# DVT-Discrete-2.net
KiCad netlist of a schematic drawn in Altium Designer
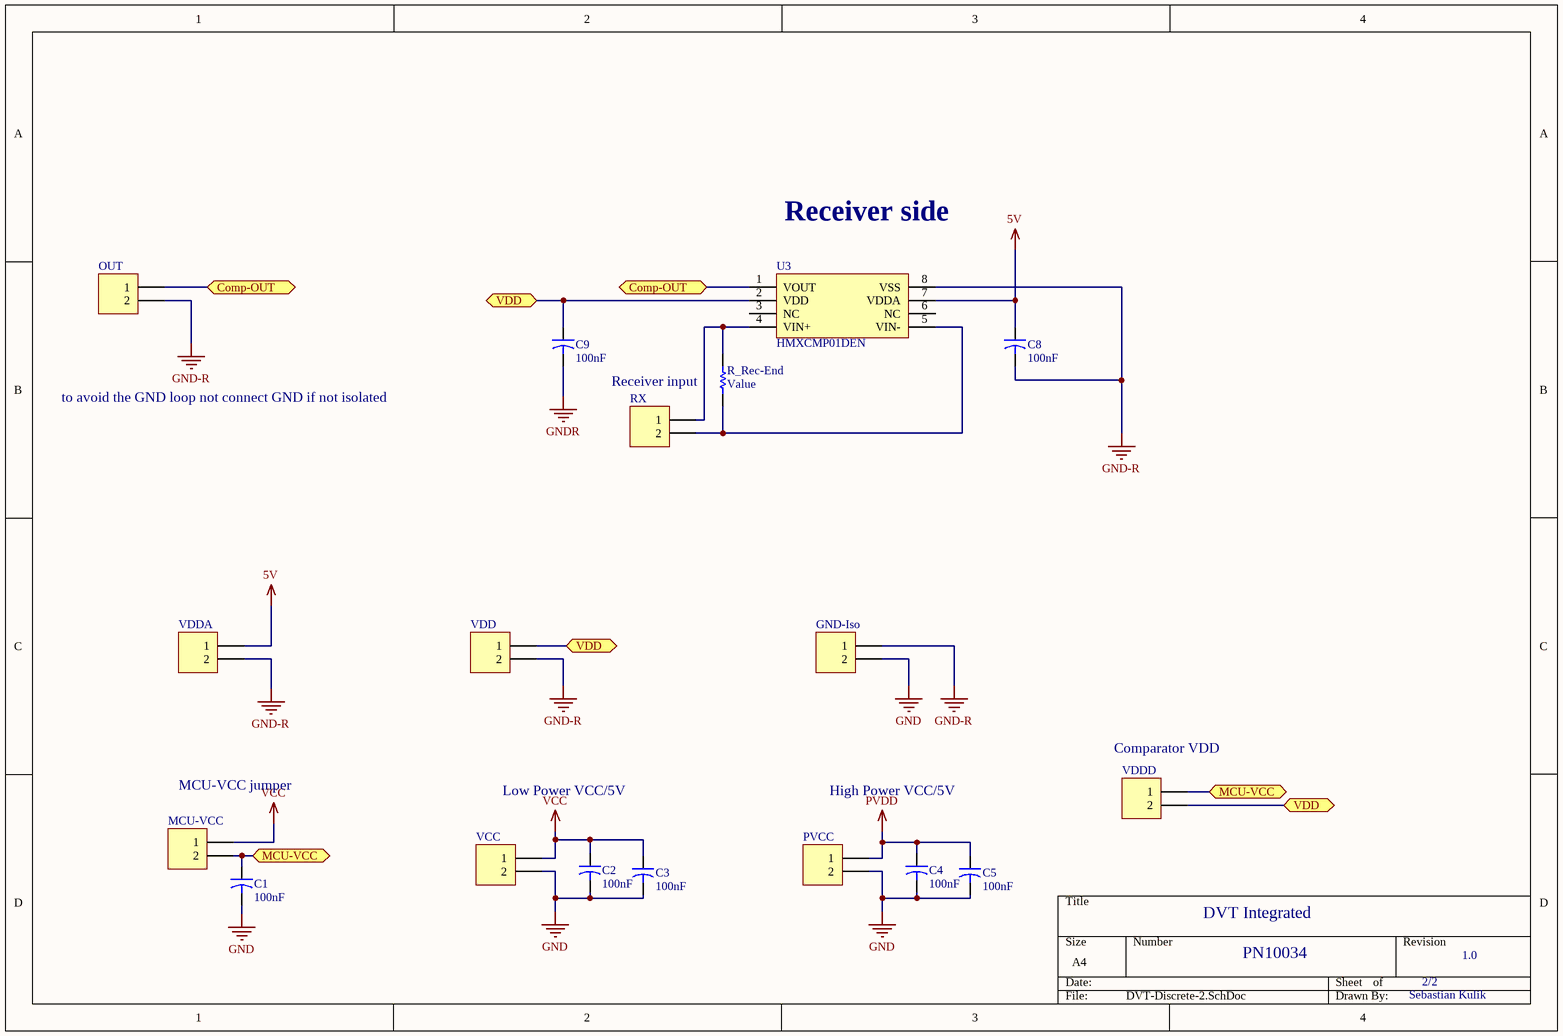
[diagram p0: DVT-Discrete-2.SchDoc]

(export (version "E")
  (design (tool "Eeschema 10.0.6"))
  (components
    (comp (ref "C1")
      (value "100nF")
      (footprint "Dummy-10mm")
      (description "Capacitor-Dummy-THT")
      (fields (field (name "MANUFACTURER") "AVX") (field (name "PUBLISHER") "Sebastian Kulik"))
      (libsource (lib "Capacitors") (part "Capacitor-Dummy-THT"))
    )
    (comp (ref "C2")
      (value "100nF")
      (footprint "Dummy-10mm")
      (description "Capacitor-Dummy-THT")
      (fields (field (name "MANUFACTURER") "AVX") (field (name "PUBLISHER") "Sebastian Kulik"))
      (libsource (lib "Capacitors") (part "Capacitor-Dummy-THT"))
    )
    (comp (ref "C3")
      (value "100nF")
      (footprint "Dummy-10mm")
      (description "Capacitor-Dummy-THT")
      (fields (field (name "MANUFACTURER") "AVX") (field (name "PUBLISHER") "Sebastian Kulik"))
      (libsource (lib "Capacitors") (part "Capacitor-Dummy-THT"))
    )
    (comp (ref "C4")
      (value "100nF")
      (footprint "Dummy-10mm")
      (description "Capacitor-Dummy-THT")
      (fields (field (name "MANUFACTURER") "AVX") (field (name "PUBLISHER") "Sebastian Kulik"))
      (libsource (lib "Capacitors") (part "Capacitor-Dummy-THT"))
    )
    (comp (ref "C5")
      (value "100nF")
      (footprint "Dummy-10mm")
      (description "Capacitor-Dummy-THT")
      (fields (field (name "MANUFACTURER") "AVX") (field (name "PUBLISHER") "Sebastian Kulik"))
      (libsource (lib "Capacitors") (part "Capacitor-Dummy-THT"))
    )
    (comp (ref "C8")
      (value "100nF")
      (footprint "Dummy-10mm")
      (description "Capacitor-Dummy-THT")
      (fields (field (name "MANUFACTURER") "AVX") (field (name "PUBLISHER") "Sebastian Kulik"))
      (libsource (lib "Capacitors") (part "Capacitor-Dummy-THT"))
    )
    (comp (ref "C9")
      (value "100nF")
      (footprint "Dummy-10mm")
      (description "Capacitor-Dummy-THT")
      (fields (field (name "MANUFACTURER") "AVX") (field (name "PUBLISHER") "Sebastian Kulik"))
      (libsource (lib "Capacitors") (part "Capacitor-Dummy-THT"))
    )
    (comp (ref "GND-Iso")
      (value "PHOENIX_1715721")
      (footprint "Phoenix-2-5_08")
      (description "Phoenix, 2 pol, 5.08mm, 22A, 715721")
      (fields (field (name "MANUFACTURER") "Phoenix") (field (name "PUBLISHER") "Sebastian Kulik"))
      (libsource (lib "Connectors") (part "2Pol_1715721"))
    )
    (comp (ref "MCU-VCC")
      (value "Plug_2_90_2.54")
      (footprint "HDR1X2")
      (description "Plug, 2-Pin")
      (fields (field (name "MANUFACTURER") "WE") (field (name "PUBLISHER") "Sebastian Kulik"))
      (libsource (lib "Connectors") (part "Plug_2_90_2.54"))
    )
    (comp (ref "OUT")
      (value "Plug_2_90_2.54")
      (footprint "HDR1X2")
      (description "Plug, 2-Pin")
      (fields (field (name "MANUFACTURER") "WE") (field (name "PUBLISHER") "Sebastian Kulik"))
      (libsource (lib "Connectors") (part "Plug_2_90_2.54"))
    )
    (comp (ref "PVCC")
      (value "PHOENIX_1715721")
      (footprint "Phoenix-2-5_08")
      (description "Phoenix, 2 pol, 5.08mm, 22A, 715721")
      (fields (field (name "MANUFACTURER") "Phoenix") (field (name "PUBLISHER") "Sebastian Kulik"))
      (libsource (lib "Connectors") (part "2Pol_1715721"))
    )
    (comp (ref "RX")
      (value "PHOENIX_1715721")
      (footprint "Phoenix-2-5_08")
      (description "Phoenix, 2 pol, 5.08mm, 22A, 715721")
      (fields (field (name "MANUFACTURER") "Phoenix") (field (name "PUBLISHER") "Sebastian Kulik"))
      (libsource (lib "Connectors") (part "2Pol_1715721"))
    )
    (comp (ref "R_Rec-End")
      (value "Value")
      (footprint "Dummy-10mm")
      (description "Resistor-Dummy-THT")
      (fields (field (name "PUBLISHER") "Sebastian Kulik"))
      (libsource (lib "Resistors") (part "Resistor-Dummy-THT"))
    )
    (comp (ref "U3")
      (value "HMXCMP01DEN")
      (footprint "Honeywell-SO8")
      (description "HiTemp Comparator")
      (fields (field (name "MANUFACTURER") "X-Rel") (field (name "PUBLISHER") "Sebastian Kulik"))
      (libsource (lib "ICs") (part "HMXCMP01DEN"))
    )
    (comp (ref "VCC")
      (value "PHOENIX_1715721")
      (footprint "Phoenix-2-5_08")
      (description "Phoenix, 2 pol, 5.08mm, 22A, 715721")
      (fields (field (name "MANUFACTURER") "Phoenix") (field (name "PUBLISHER") "Sebastian Kulik"))
      (libsource (lib "Connectors") (part "2Pol_1715721"))
    )
    (comp (ref "VDD")
      (value "PHOENIX_1715721")
      (footprint "Phoenix-2-5_08")
      (description "Phoenix, 2 pol, 5.08mm, 22A, 715721")
      (fields (field (name "MANUFACTURER") "Phoenix") (field (name "PUBLISHER") "Sebastian Kulik"))
      (libsource (lib "Connectors") (part "2Pol_1715721"))
    )
    (comp (ref "VDDA")
      (value "PHOENIX_1715721")
      (footprint "Phoenix-2-5_08")
      (description "Phoenix, 2 pol, 5.08mm, 22A, 715721")
      (fields (field (name "MANUFACTURER") "Phoenix") (field (name "PUBLISHER") "Sebastian Kulik"))
      (libsource (lib "Connectors") (part "2Pol_1715721"))
    )
    (comp (ref "VDDD")
      (value "Plug_2_90_2.54")
      (footprint "HDR1X2")
      (description "Plug, 2-Pin")
      (fields (field (name "MANUFACTURER") "WE") (field (name "PUBLISHER") "Sebastian Kulik"))
      (libsource (lib "Connectors") (part "Plug_2_90_2.54"))
    )
  )
  (nets
    (net (code "1") (name "/Comp-OUT") (class "Default")
      (node (ref "OUT") (pin "1") (pinfunction "1_1") (pintype "passive"))
      (node (ref "U3") (pin "1") (pinfunction "VOUT_1") (pintype "passive"))
    )
    (net (code "2") (name "/MCU-VCC") (class "Default")
      (node (ref "C1") (pin "1") (pinfunction "1_1") (pintype "passive"))
      (node (ref "MCU-VCC") (pin "2") (pinfunction "2_2") (pintype "passive"))
      (node (ref "VDDD") (pin "1") (pinfunction "1_1") (pintype "passive"))
    )
    (net (code "3") (name "/VDD") (class "Default")
      (node (ref "C9") (pin "1") (pinfunction "1_1") (pintype "passive"))
      (node (ref "U3") (pin "2") (pinfunction "VDD_2") (pintype "passive"))
      (node (ref "VDD") (pin "1") (pinfunction "1_1") (pintype "passive"))
      (node (ref "VDDD") (pin "2") (pinfunction "2_2") (pintype "passive"))
    )
    (net (code "4") (name "5V") (class "Default")
      (node (ref "C8") (pin "1") (pinfunction "1_1") (pintype "passive"))
      (node (ref "U3") (pin "7") (pinfunction "VDDA_7") (pintype "passive"))
      (node (ref "VDDA") (pin "1") (pinfunction "1_1") (pintype "passive"))
    )
    (net (code "5") (name "GND") (class "Default")
      (node (ref "C1") (pin "2") (pinfunction "2_2") (pintype "passive"))
      (node (ref "C2") (pin "2") (pinfunction "2_2") (pintype "passive"))
      (node (ref "C3") (pin "2") (pinfunction "2_2") (pintype "passive"))
      (node (ref "C4") (pin "2") (pinfunction "2_2") (pintype "passive"))
      (node (ref "C5") (pin "2") (pinfunction "2_2") (pintype "passive"))
      (node (ref "GND-Iso") (pin "2") (pinfunction "2_2") (pintype "passive"))
      (node (ref "PVCC") (pin "2") (pinfunction "2_2") (pintype "passive"))
      (node (ref "VCC") (pin "2") (pinfunction "2_2") (pintype "passive"))
    )
    (net (code "6") (name "GND-R") (class "Default")
      (node (ref "C8") (pin "2") (pinfunction "2_2") (pintype "passive"))
      (node (ref "GND-Iso") (pin "1") (pinfunction "1_1") (pintype "passive"))
      (node (ref "OUT") (pin "2") (pinfunction "2_2") (pintype "passive"))
      (node (ref "U3") (pin "8") (pinfunction "VSS_8") (pintype "passive"))
      (node (ref "VDD") (pin "2") (pinfunction "2_2") (pintype "passive"))
      (node (ref "VDDA") (pin "2") (pinfunction "2_2") (pintype "passive"))
    )
    (net (code "7") (name "GNDR") (class "Default")
      (node (ref "C9") (pin "2") (pinfunction "2_2") (pintype "passive"))
    )
    (net (code "8") (name "Net-(U3-VIN+)") (class "Default")
      (node (ref "RX") (pin "1") (pinfunction "1_1") (pintype "passive"))
      (node (ref "R_Rec-End") (pin "2") (pinfunction "2_2") (pintype "passive"))
      (node (ref "U3") (pin "4") (pinfunction "VIN+_4") (pintype "passive"))
    )
    (net (code "9") (name "Net-(U3-VIN-)") (class "Default")
      (node (ref "RX") (pin "2") (pinfunction "2_2") (pintype "passive"))
      (node (ref "R_Rec-End") (pin "1") (pinfunction "1_1") (pintype "passive"))
      (node (ref "U3") (pin "5") (pinfunction "VIN-_5") (pintype "passive"))
    )
    (net (code "10") (name "PVDD") (class "Default")
      (node (ref "C4") (pin "1") (pinfunction "1_1") (pintype "passive"))
      (node (ref "C5") (pin "1") (pinfunction "1_1") (pintype "passive"))
      (node (ref "PVCC") (pin "1") (pinfunction "1_1") (pintype "passive"))
    )
    (net (code "11") (name "VCC") (class "Default")
      (node (ref "C2") (pin "1") (pinfunction "1_1") (pintype "passive"))
      (node (ref "C3") (pin "1") (pinfunction "1_1") (pintype "passive"))
      (node (ref "MCU-VCC") (pin "1") (pinfunction "1_1") (pintype "passive"))
      (node (ref "VCC") (pin "1") (pinfunction "1_1") (pintype "passive"))
    )
    (net (code "12") (name "unconnected-(U3-NC-Pad3)") (class "Default")
      (node (ref "U3") (pin "3") (pinfunction "NC_3") (pintype "passive"))
    )
    (net (code "13") (name "unconnected-(U3-NC-Pad6)") (class "Default")
      (node (ref "U3") (pin "6") (pinfunction "NC_6") (pintype "passive"))
    )
  )
)
